# LPEM.net
KiCad netlist of a schematic drawn in EAGLE
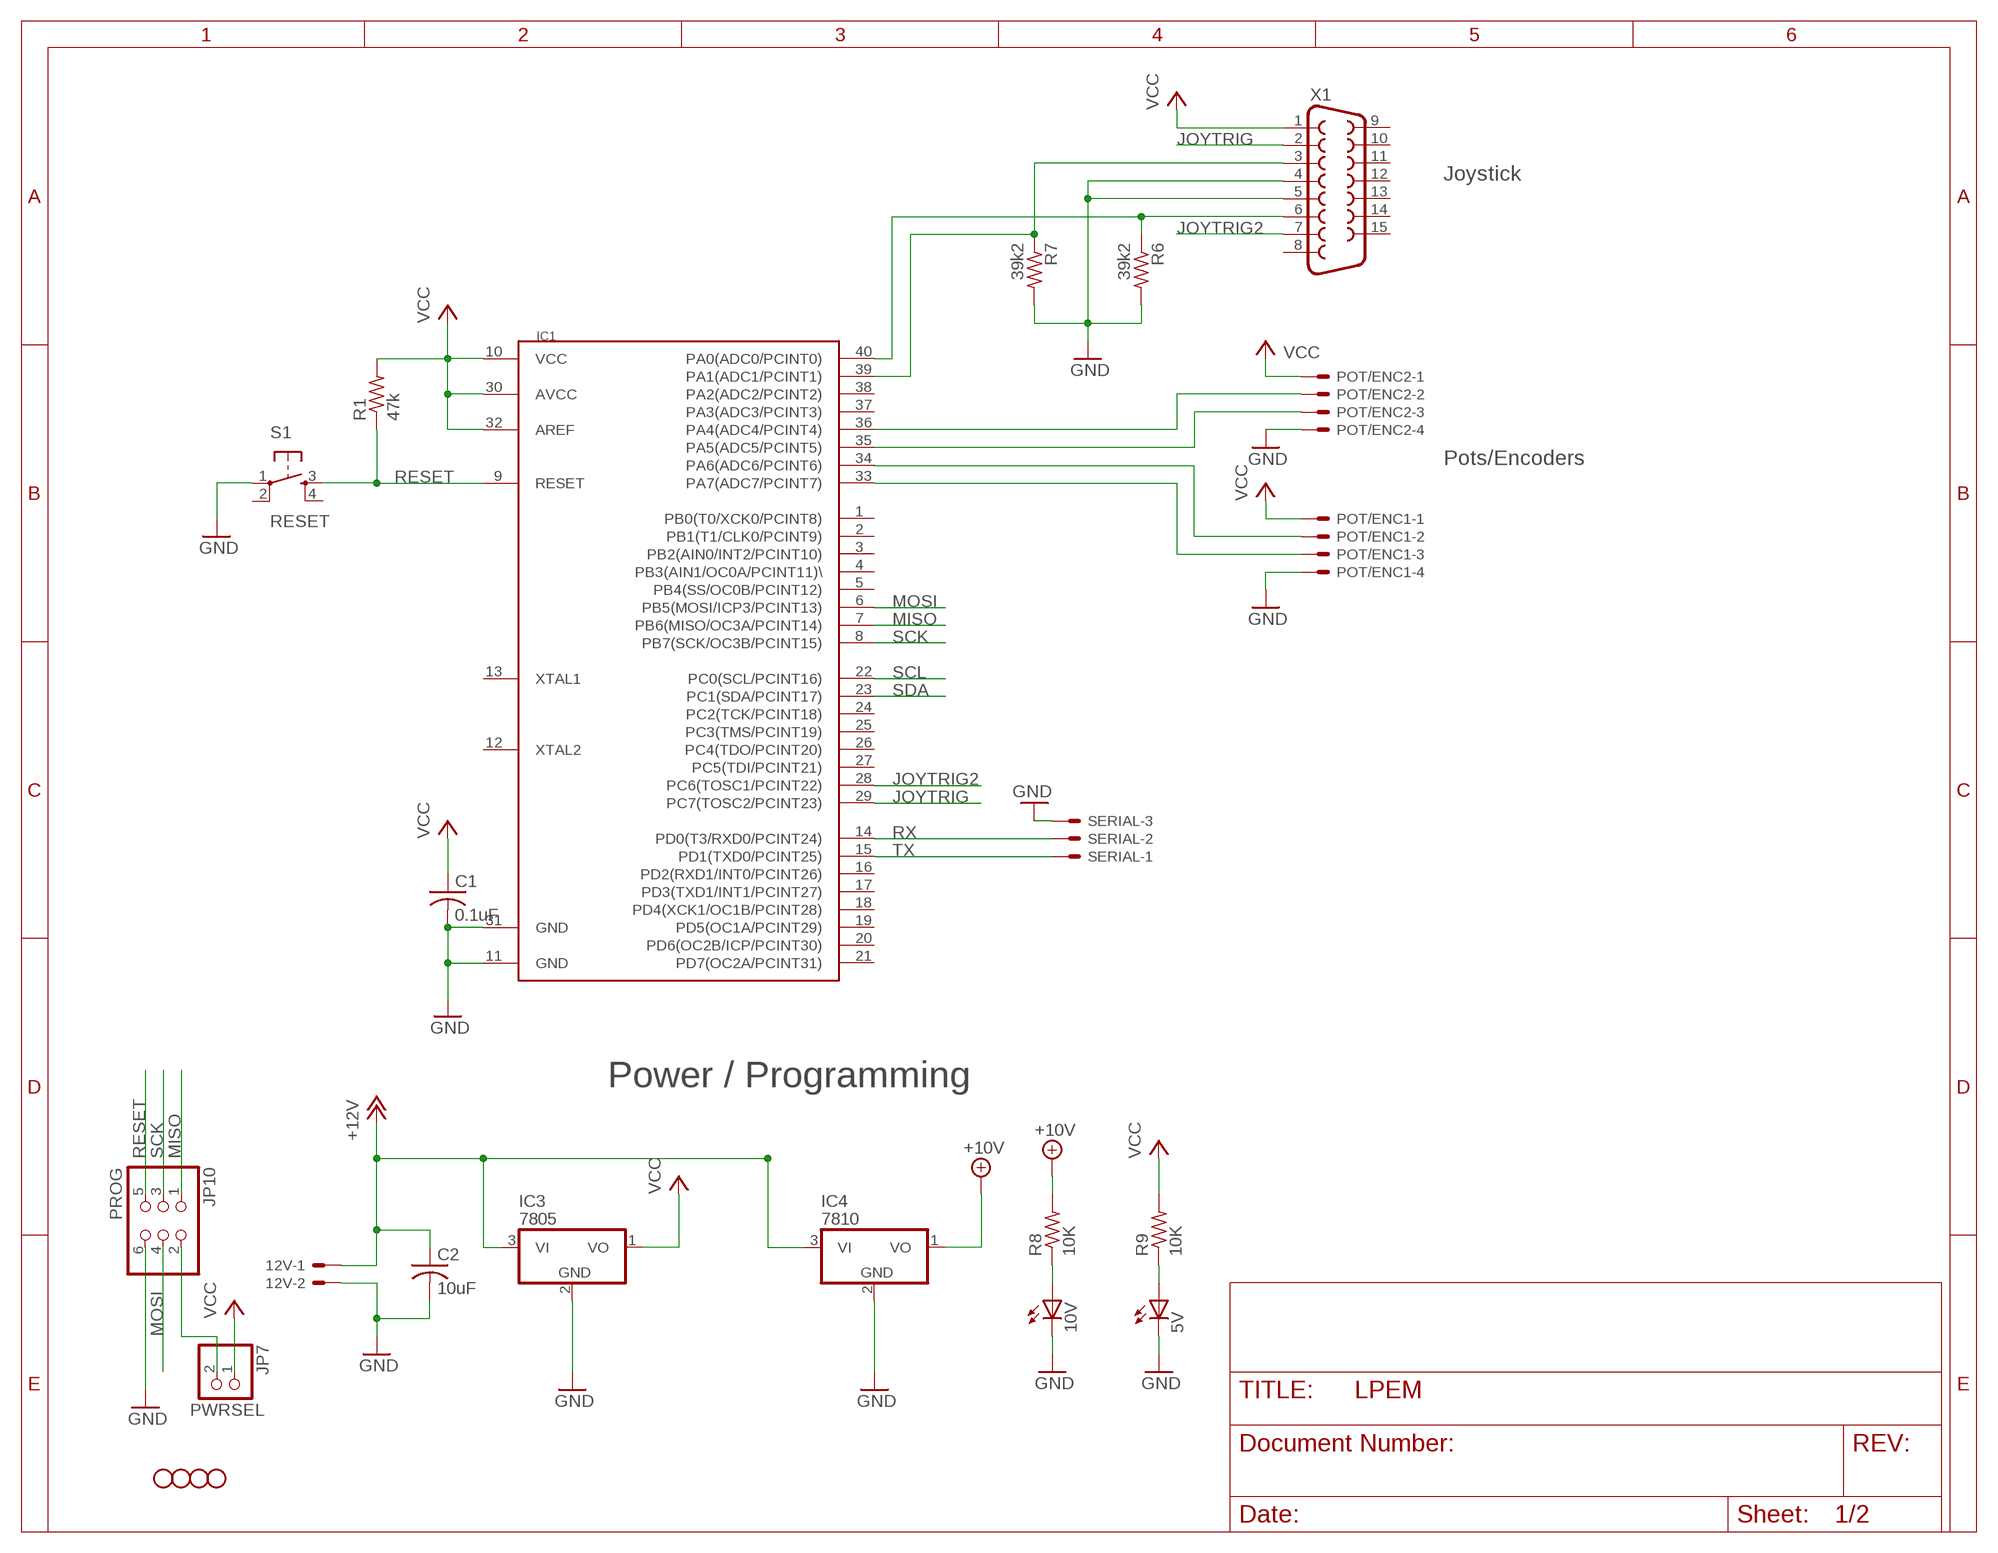
[diagram p0: schematic, sheet 1]
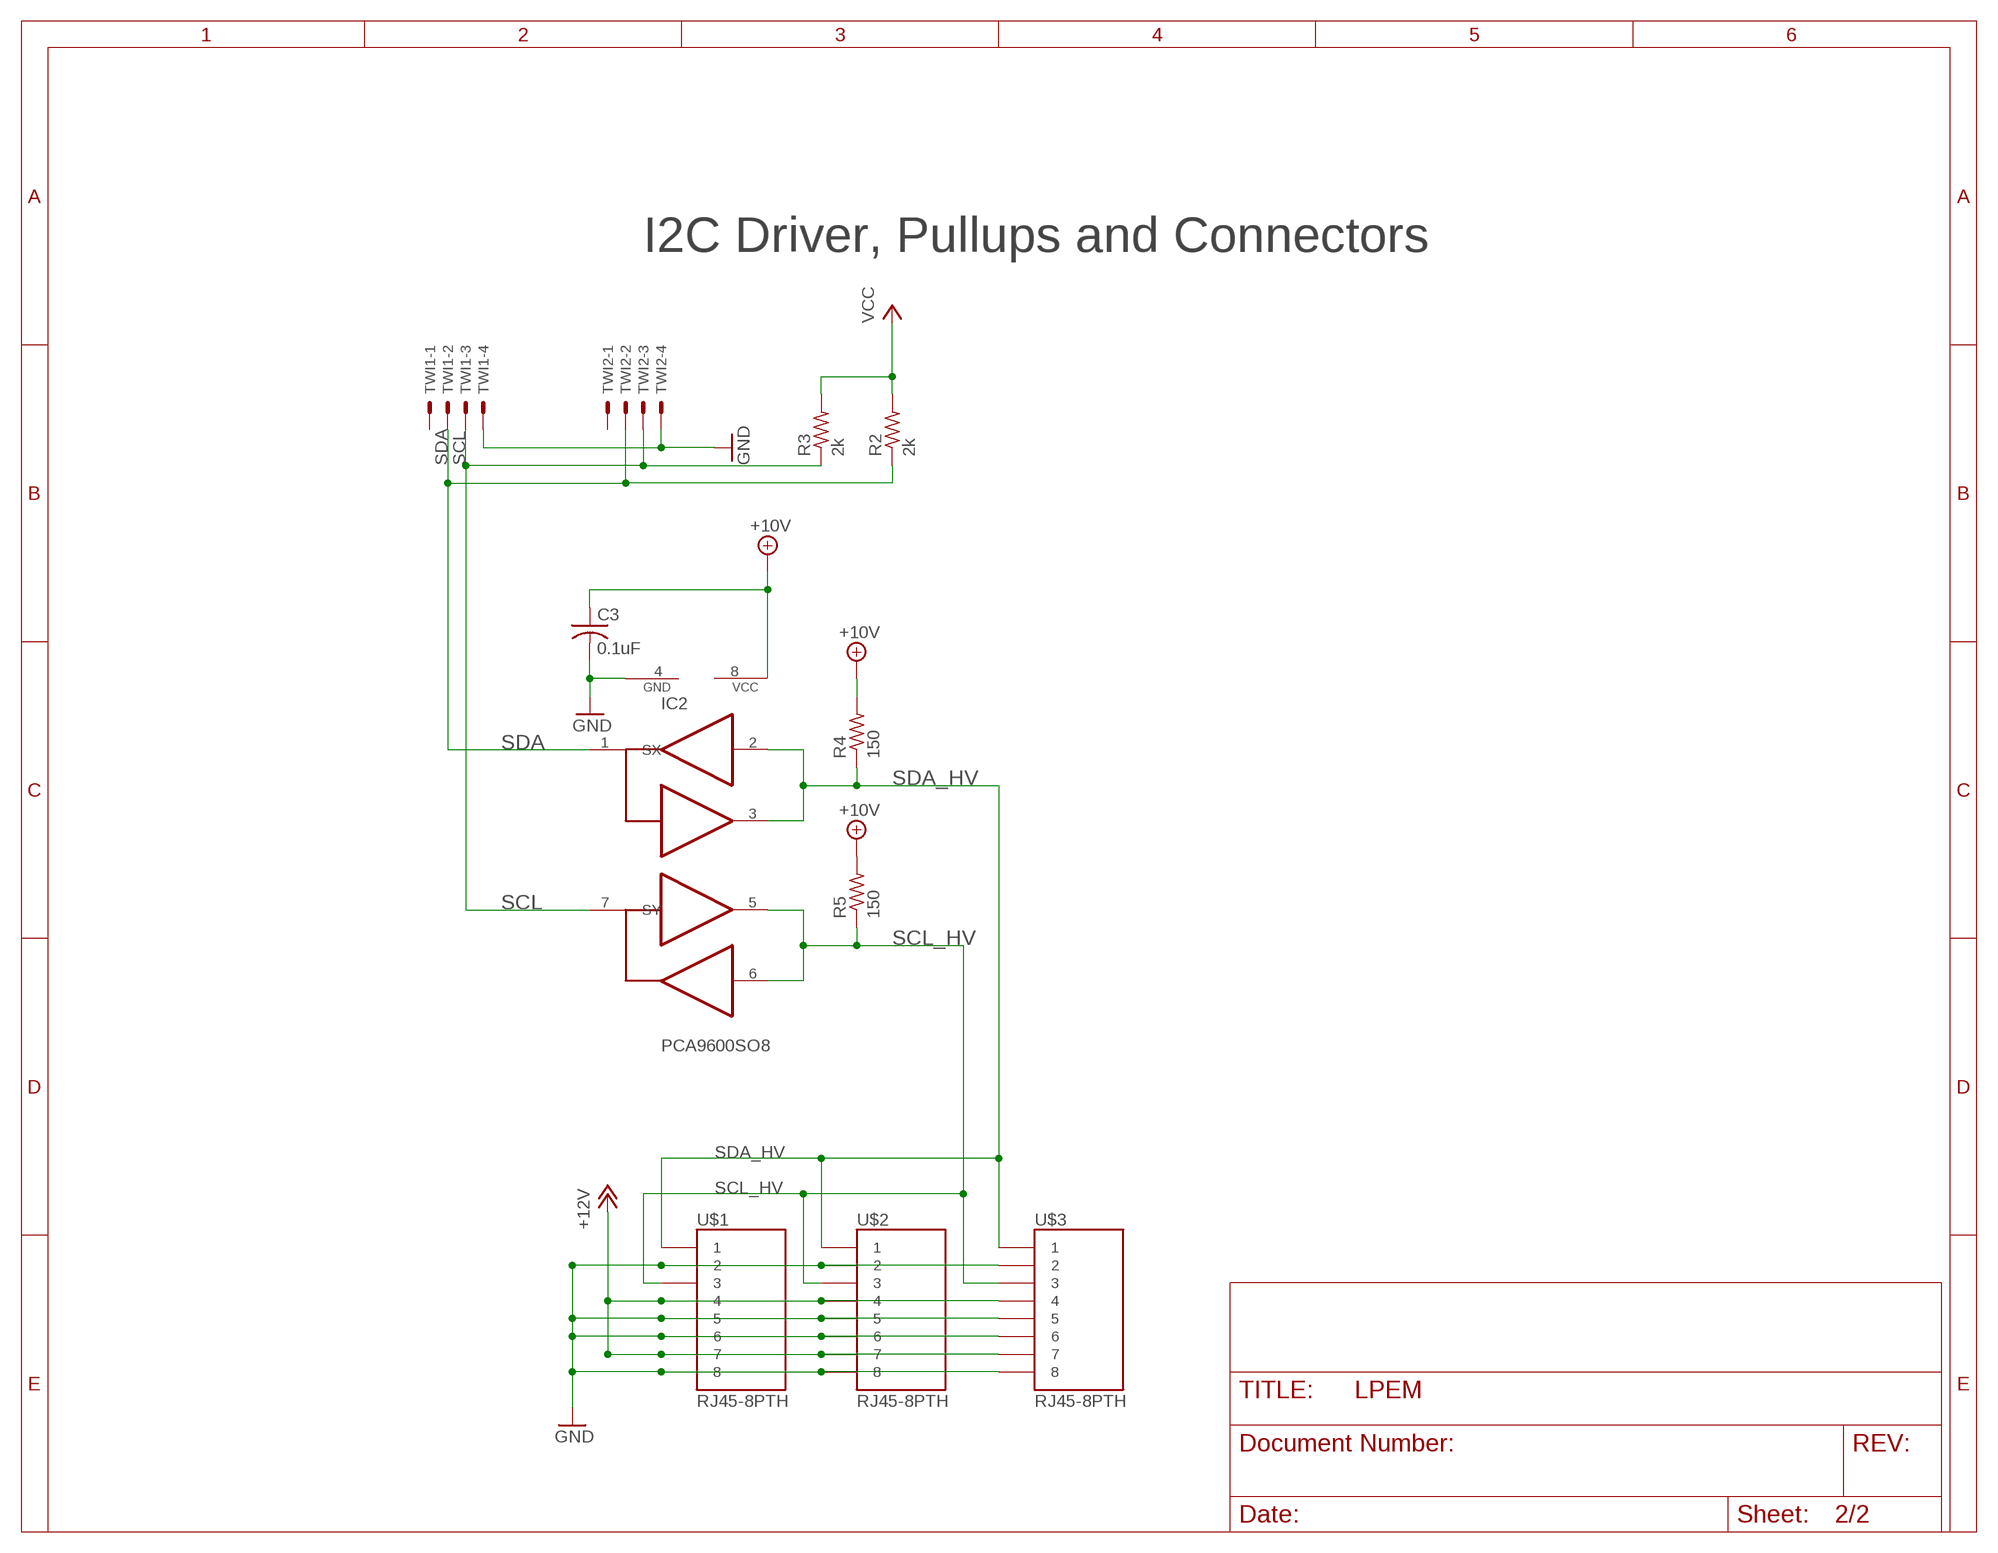
[diagram p1: schematic, sheet 2]

(export (version "E")
  (design (tool "Eeschema 10.0.6"))
  (components
    (comp (ref "5V")
      (value "LED3MM")
      (footprint "eagle-import:LED3MM")
      (libsource (lib "eagle-import") (part "LED3MM"))
    )
    (comp (ref "10V")
      (value "LED3MM")
      (footprint "eagle-import:LED3MM")
      (libsource (lib "eagle-import") (part "LED3MM"))
    )
    (comp (ref "12V")
      (value "22-23-2021")
      (footprint "eagle-import:22-23-2021")
      (fields (field (name "MF") "MOLEX"))
      (libsource (lib "eagle-import") (part "22-23-2021"))
    )
    (comp (ref "C1")
      (value "0.1uF")
      (footprint "eagle-import:C025-025X050")
      (libsource (lib "eagle-import") (part "C-US025-025X050"))
    )
    (comp (ref "C2")
      (value "10uF")
      (footprint "eagle-import:C025-025X050")
      (libsource (lib "eagle-import") (part "C-US025-025X050"))
    )
    (comp (ref "IC1")
      (value "MEGA1284P")
      (footprint "eagle-import:DIL40")
      (libsource (lib "eagle-import") (part "MEGA1284P"))
    )
    (comp (ref "IC3")
      (value "7805")
      (footprint "eagle-import:TO92")
      (libsource (lib "eagle-import") (part "78ZL05"))
    )
    (comp (ref "IC4")
      (value "7810")
      (footprint "eagle-import:TO92")
      (libsource (lib "eagle-import") (part "78ZL05"))
    )
    (comp (ref "JP1")
      (value "STAND-OFF")
      (footprint "eagle-import:STAND-OFF")
      (libsource (lib "eagle-import") (part "STAND-OFF"))
    )
    (comp (ref "JP2")
      (value "STAND-OFF")
      (footprint "eagle-import:STAND-OFF")
      (libsource (lib "eagle-import") (part "STAND-OFF"))
    )
    (comp (ref "JP7")
      (value "PWRSEL")
      (footprint "eagle-import:1X02")
      (libsource (lib "eagle-import") (part "PINHD-1X2"))
    )
    (comp (ref "JP8")
      (value "STAND-OFF")
      (footprint "eagle-import:STAND-OFF")
      (libsource (lib "eagle-import") (part "STAND-OFF"))
    )
    (comp (ref "JP9")
      (value "STAND-OFF")
      (footprint "eagle-import:STAND-OFF")
      (libsource (lib "eagle-import") (part "STAND-OFF"))
    )
    (comp (ref "JP10")
      (value "PROG")
      (footprint "eagle-import:2X03")
      (libsource (lib "eagle-import") (part "PINHD-2X3"))
    )
    (comp (ref "POT/ENC1")
      (value "22-23-2041")
      (footprint "eagle-import:22-23-2041")
      (fields (field (name "MF") "MOLEX"))
      (libsource (lib "eagle-import") (part "22-23-2041"))
    )
    (comp (ref "POT/ENC2")
      (value "22-23-2041")
      (footprint "eagle-import:22-23-2041")
      (fields (field (name "MF") "MOLEX"))
      (libsource (lib "eagle-import") (part "22-23-2041"))
    )
    (comp (ref "R1")
      (value "47k")
      (footprint "eagle-import:0204_5")
      (libsource (lib "eagle-import") (part "R-US_0204/5"))
    )
    (comp (ref "R6")
      (value "39k2")
      (footprint "eagle-import:0204_5")
      (libsource (lib "eagle-import") (part "R-US_0204/5"))
    )
    (comp (ref "R7")
      (value "39k2")
      (footprint "eagle-import:0204_5")
      (libsource (lib "eagle-import") (part "R-US_0204/5"))
    )
    (comp (ref "R8")
      (value "10K")
      (footprint "eagle-import:0204_5")
      (libsource (lib "eagle-import") (part "R-US_0204/5"))
    )
    (comp (ref "R9")
      (value "10K")
      (footprint "eagle-import:0204_5")
      (libsource (lib "eagle-import") (part "R-US_0204/5"))
    )
    (comp (ref "S1")
      (value "RESET")
      (footprint "eagle-import:TACTILE-PTH")
      (libsource (lib "eagle-import") (part "TAC_SWITCHPTH"))
    )
    (comp (ref "SERIAL")
      (value "22-23-2031")
      (footprint "eagle-import:22-23-2031")
      (fields (field (name "MF") "MOLEX"))
      (libsource (lib "eagle-import") (part "22-23-2031"))
    )
    (comp (ref "X1")
      (value "F15HP")
      (footprint "eagle-import:F15HP")
      (libsource (lib "eagle-import") (part "F15HP"))
    )
    (comp (ref "C3")
      (value "0.1uF")
      (footprint "eagle-import:C025-025X050")
      (libsource (lib "eagle-import") (part "C-US025-025X050"))
    )
    (comp (ref "IC2")
      (value "PCA9600SO8")
      (footprint "eagle-import:SO08")
      (libsource (lib "eagle-import") (part "PCA9600SO8"))
    )
    (comp (ref "R2")
      (value "2k")
      (footprint "eagle-import:0204_5")
      (libsource (lib "eagle-import") (part "R-US_0204/5"))
    )
    (comp (ref "R3")
      (value "2k")
      (footprint "eagle-import:0204_5")
      (libsource (lib "eagle-import") (part "R-US_0204/5"))
    )
    (comp (ref "R4")
      (value "150")
      (footprint "eagle-import:0204_5")
      (libsource (lib "eagle-import") (part "R-US_0204/5"))
    )
    (comp (ref "R5")
      (value "150")
      (footprint "eagle-import:0204_5")
      (libsource (lib "eagle-import") (part "R-US_0204/5"))
    )
    (comp (ref "TWI1")
      (value "22-23-2041")
      (footprint "eagle-import:22-23-2041")
      (fields (field (name "MF") "MOLEX"))
      (libsource (lib "eagle-import") (part "22-23-2041"))
    )
    (comp (ref "TWI2")
      (value "22-23-2041")
      (footprint "eagle-import:22-23-2041")
      (fields (field (name "MF") "MOLEX"))
      (libsource (lib "eagle-import") (part "22-23-2041"))
    )
    (comp (ref "U$1")
      (value "RJ45-8PTH")
      (footprint "eagle-import:RJ45-8")
      (libsource (lib "eagle-import") (part "RJ45-8PTH"))
    )
    (comp (ref "U$2")
      (value "RJ45-8PTH")
      (footprint "eagle-import:RJ45-8")
      (libsource (lib "eagle-import") (part "RJ45-8PTH"))
    )
    (comp (ref "U$3")
      (value "RJ45-8PTH")
      (footprint "eagle-import:RJ45-8")
      (libsource (lib "eagle-import") (part "RJ45-8PTH"))
    )
  )
  (nets
    (net (code "1") (name "+10V") (class "Default")
      (node (ref "C3") (pin "1") (pinfunction "1_1") (pintype "passive"))
      (node (ref "IC2") (pin "8") (pinfunction "VCC_8") (pintype "power_in"))
      (node (ref "IC4") (pin "1") (pinfunction "VO_1") (pintype "passive"))
      (node (ref "R4") (pin "2") (pinfunction "2_2") (pintype "passive"))
      (node (ref "R5") (pin "2") (pinfunction "2_2") (pintype "passive"))
      (node (ref "R8") (pin "2") (pinfunction "2_2") (pintype "passive"))
    )
    (net (code "2") (name "+12V") (class "Default")
      (node (ref "12V") (pin "1") (pinfunction "S_1") (pintype "passive"))
      (node (ref "C2") (pin "1") (pinfunction "1_1") (pintype "passive"))
      (node (ref "IC3") (pin "3") (pinfunction "VI_3") (pintype "input"))
      (node (ref "IC4") (pin "3") (pinfunction "VI_3") (pintype "input"))
      (node (ref "U$1") (pin "4") (pinfunction "4_4") (pintype "bidirectional"))
      (node (ref "U$1") (pin "7") (pinfunction "7_7") (pintype "bidirectional"))
      (node (ref "U$2") (pin "4") (pinfunction "4_4") (pintype "bidirectional"))
      (node (ref "U$2") (pin "7") (pinfunction "7_7") (pintype "bidirectional"))
      (node (ref "U$3") (pin "4") (pinfunction "4_4") (pintype "bidirectional"))
      (node (ref "U$3") (pin "7") (pinfunction "7_7") (pintype "bidirectional"))
    )
    (net (code "3") (name "GND") (class "Default")
      (node (ref "10V") (pin "K") (pinfunction "C_K") (pintype "passive"))
      (node (ref "12V") (pin "2") (pinfunction "S_2") (pintype "passive"))
      (node (ref "5V") (pin "K") (pinfunction "C_K") (pintype "passive"))
      (node (ref "C1") (pin "2") (pinfunction "2_2") (pintype "passive"))
      (node (ref "C2") (pin "2") (pinfunction "2_2") (pintype "passive"))
      (node (ref "C3") (pin "2") (pinfunction "2_2") (pintype "passive"))
      (node (ref "IC1") (pin "11") (pinfunction "GND_11") (pintype "bidirectional"))
      (node (ref "IC1") (pin "31") (pinfunction "GND_31") (pintype "bidirectional"))
      (node (ref "IC2") (pin "4") (pinfunction "GND_4") (pintype "power_in"))
      (node (ref "IC3") (pin "2") (pinfunction "GND_2") (pintype "passive"))
      (node (ref "IC4") (pin "2") (pinfunction "GND_2") (pintype "passive"))
      (node (ref "JP10") (pin "6") (pinfunction "6_6") (pintype "passive"))
      (node (ref "POT/ENC1") (pin "4") (pinfunction "S_4") (pintype "passive"))
      (node (ref "POT/ENC2") (pin "4") (pinfunction "S_4") (pintype "passive"))
      (node (ref "R6") (pin "2") (pinfunction "2_2") (pintype "passive"))
      (node (ref "R7") (pin "2") (pinfunction "2_2") (pintype "passive"))
      (node (ref "S1") (pin "1") (pinfunction "1_1") (pintype "passive"))
      (node (ref "SERIAL") (pin "3") (pinfunction "S_3") (pintype "passive"))
      (node (ref "TWI1") (pin "4") (pinfunction "S_4") (pintype "passive"))
      (node (ref "TWI2") (pin "4") (pinfunction "S_4") (pintype "passive"))
      (node (ref "U$1") (pin "2") (pinfunction "2_2") (pintype "bidirectional"))
      (node (ref "U$1") (pin "5") (pinfunction "5_5") (pintype "bidirectional"))
      (node (ref "U$1") (pin "6") (pinfunction "6_6") (pintype "bidirectional"))
      (node (ref "U$1") (pin "8") (pinfunction "8_8") (pintype "bidirectional"))
      (node (ref "U$2") (pin "2") (pinfunction "2_2") (pintype "bidirectional"))
      (node (ref "U$2") (pin "5") (pinfunction "5_5") (pintype "bidirectional"))
      (node (ref "U$2") (pin "6") (pinfunction "6_6") (pintype "bidirectional"))
      (node (ref "U$2") (pin "8") (pinfunction "8_8") (pintype "bidirectional"))
      (node (ref "U$3") (pin "2") (pinfunction "2_2") (pintype "bidirectional"))
      (node (ref "U$3") (pin "5") (pinfunction "5_5") (pintype "bidirectional"))
      (node (ref "U$3") (pin "6") (pinfunction "6_6") (pintype "bidirectional"))
      (node (ref "U$3") (pin "8") (pinfunction "8_8") (pintype "bidirectional"))
      (node (ref "X1") (pin "4") (pinfunction "4_4") (pintype "passive"))
      (node (ref "X1") (pin "5") (pinfunction "5_5") (pintype "passive"))
    )
    (net (code "4") (name "JOYTRIG") (class "Default")
      (node (ref "IC1") (pin "29") (pinfunction "PC7(TOSC2/PCINT23)_29") (pintype "bidirectional"))
      (node (ref "X1") (pin "2") (pinfunction "2_2") (pintype "passive"))
    )
    (net (code "5") (name "JOYTRIG2") (class "Default")
      (node (ref "IC1") (pin "28") (pinfunction "PC6(TOSC1/PCINT22)_28") (pintype "bidirectional"))
      (node (ref "X1") (pin "7") (pinfunction "7_7") (pintype "passive"))
    )
    (net (code "6") (name "MISO") (class "Default")
      (node (ref "IC1") (pin "7") (pinfunction "PB6(MISO/OC3A/PCINT14)_7") (pintype "bidirectional"))
      (node (ref "JP10") (pin "1") (pinfunction "1_1") (pintype "passive"))
    )
    (net (code "7") (name "MOSI") (class "Default")
      (node (ref "IC1") (pin "6") (pinfunction "PB5(MOSI/ICP3/PCINT13)_6") (pintype "bidirectional"))
      (node (ref "JP10") (pin "4") (pinfunction "4_4") (pintype "passive"))
    )
    (net (code "8") (name "Net-(5V-PadA)") (class "Default")
      (node (ref "5V") (pin "A") (pinfunction "A_A") (pintype "passive"))
      (node (ref "R9") (pin "1") (pinfunction "1_1") (pintype "passive"))
    )
    (net (code "9") (name "Net-(10V-PadA)") (class "Default")
      (node (ref "10V") (pin "A") (pinfunction "A_A") (pintype "passive"))
      (node (ref "R8") (pin "1") (pinfunction "1_1") (pintype "passive"))
    )
    (net (code "10") (name "Net-(IC1-PA0(ADC0{slash}PCINT0))") (class "Default")
      (node (ref "IC1") (pin "40") (pinfunction "PA0(ADC0/PCINT0)_40") (pintype "bidirectional"))
      (node (ref "R6") (pin "1") (pinfunction "1_1") (pintype "passive"))
      (node (ref "X1") (pin "6") (pinfunction "6_6") (pintype "passive"))
    )
    (net (code "11") (name "Net-(IC1-PA1(ADC1{slash}PCINT1))") (class "Default")
      (node (ref "IC1") (pin "39") (pinfunction "PA1(ADC1/PCINT1)_39") (pintype "bidirectional"))
      (node (ref "R7") (pin "1") (pinfunction "1_1") (pintype "passive"))
      (node (ref "X1") (pin "3") (pinfunction "3_3") (pintype "passive"))
    )
    (net (code "12") (name "Net-(IC1-PA4(ADC4{slash}PCINT4))") (class "Default")
      (node (ref "IC1") (pin "36") (pinfunction "PA4(ADC4/PCINT4)_36") (pintype "bidirectional"))
      (node (ref "POT/ENC2") (pin "2") (pinfunction "S_2") (pintype "passive"))
    )
    (net (code "13") (name "Net-(IC1-PA5(ADC5{slash}PCINT5))") (class "Default")
      (node (ref "IC1") (pin "35") (pinfunction "PA5(ADC5/PCINT5)_35") (pintype "bidirectional"))
      (node (ref "POT/ENC2") (pin "3") (pinfunction "S_3") (pintype "passive"))
    )
    (net (code "14") (name "Net-(IC1-PA6(ADC6{slash}PCINT6))") (class "Default")
      (node (ref "IC1") (pin "34") (pinfunction "PA6(ADC6/PCINT6)_34") (pintype "bidirectional"))
      (node (ref "POT/ENC1") (pin "2") (pinfunction "S_2") (pintype "passive"))
    )
    (net (code "15") (name "Net-(IC1-PA7(ADC7{slash}PCINT7))") (class "Default")
      (node (ref "IC1") (pin "33") (pinfunction "PA7(ADC7/PCINT7)_33") (pintype "bidirectional"))
      (node (ref "POT/ENC1") (pin "3") (pinfunction "S_3") (pintype "passive"))
    )
    (net (code "16") (name "Net-(JP10-Pad2)") (class "Default")
      (node (ref "JP10") (pin "2") (pinfunction "2_2") (pintype "passive"))
      (node (ref "JP7") (pin "2") (pinfunction "2_2") (pintype "passive"))
    )
    (net (code "17") (name "RESET") (class "Default")
      (node (ref "IC1") (pin "9") (pinfunction "RESET_9") (pintype "bidirectional"))
      (node (ref "JP10") (pin "5") (pinfunction "5_5") (pintype "passive"))
      (node (ref "R1") (pin "1") (pinfunction "1_1") (pintype "passive"))
      (node (ref "S1") (pin "3") (pinfunction "3_3") (pintype "passive"))
    )
    (net (code "18") (name "RX") (class "Default")
      (node (ref "IC1") (pin "14") (pinfunction "PD0(T3/RXD0/PCINT24)_14") (pintype "bidirectional"))
      (node (ref "SERIAL") (pin "2") (pinfunction "S_2") (pintype "passive"))
    )
    (net (code "19") (name "SCK") (class "Default")
      (node (ref "IC1") (pin "8") (pinfunction "PB7(SCK/OC3B/PCINT15)_8") (pintype "bidirectional"))
      (node (ref "JP10") (pin "3") (pinfunction "3_3") (pintype "passive"))
    )
    (net (code "20") (name "SCL") (class "Default")
      (node (ref "IC1") (pin "22") (pinfunction "PC0(SCL/PCINT16)_22") (pintype "bidirectional"))
      (node (ref "IC2") (pin "7") (pinfunction "SY_7") (pintype "bidirectional"))
      (node (ref "R3") (pin "1") (pinfunction "1_1") (pintype "passive"))
      (node (ref "TWI1") (pin "3") (pinfunction "S_3") (pintype "passive"))
      (node (ref "TWI2") (pin "3") (pinfunction "S_3") (pintype "passive"))
    )
    (net (code "21") (name "SCL_HV") (class "Default")
      (node (ref "IC2") (pin "5") (pinfunction "TY_5") (pintype "output"))
      (node (ref "IC2") (pin "6") (pinfunction "RY_6") (pintype "input"))
      (node (ref "R5") (pin "1") (pinfunction "1_1") (pintype "passive"))
      (node (ref "U$1") (pin "3") (pinfunction "3_3") (pintype "bidirectional"))
      (node (ref "U$2") (pin "3") (pinfunction "3_3") (pintype "bidirectional"))
      (node (ref "U$3") (pin "3") (pinfunction "3_3") (pintype "bidirectional"))
    )
    (net (code "22") (name "SDA") (class "Default")
      (node (ref "IC1") (pin "23") (pinfunction "PC1(SDA/PCINT17)_23") (pintype "bidirectional"))
      (node (ref "IC2") (pin "1") (pinfunction "SX_1") (pintype "bidirectional"))
      (node (ref "R2") (pin "1") (pinfunction "1_1") (pintype "passive"))
      (node (ref "TWI1") (pin "2") (pinfunction "S_2") (pintype "passive"))
      (node (ref "TWI2") (pin "2") (pinfunction "S_2") (pintype "passive"))
    )
    (net (code "23") (name "SDA_HV") (class "Default")
      (node (ref "IC2") (pin "2") (pinfunction "RX_2") (pintype "input"))
      (node (ref "IC2") (pin "3") (pinfunction "TX_3") (pintype "output"))
      (node (ref "R4") (pin "1") (pinfunction "1_1") (pintype "passive"))
      (node (ref "U$1") (pin "1") (pinfunction "1_1") (pintype "bidirectional"))
      (node (ref "U$2") (pin "1") (pinfunction "1_1") (pintype "bidirectional"))
      (node (ref "U$3") (pin "1") (pinfunction "1_1") (pintype "bidirectional"))
    )
    (net (code "24") (name "TX") (class "Default")
      (node (ref "IC1") (pin "15") (pinfunction "PD1(TXD0/PCINT25)_15") (pintype "bidirectional"))
      (node (ref "SERIAL") (pin "1") (pinfunction "S_1") (pintype "passive"))
    )
    (net (code "25") (name "VCC") (class "Default")
      (node (ref "C1") (pin "1") (pinfunction "1_1") (pintype "passive"))
      (node (ref "IC1") (pin "10") (pinfunction "VCC_10") (pintype "bidirectional"))
      (node (ref "IC1") (pin "30") (pinfunction "AVCC_30") (pintype "bidirectional"))
      (node (ref "IC1") (pin "32") (pinfunction "AREF_32") (pintype "bidirectional"))
      (node (ref "IC3") (pin "1") (pinfunction "VO_1") (pintype "passive"))
      (node (ref "JP7") (pin "1") (pinfunction "1_1") (pintype "passive"))
      (node (ref "POT/ENC1") (pin "1") (pinfunction "S_1") (pintype "passive"))
      (node (ref "POT/ENC2") (pin "1") (pinfunction "S_1") (pintype "passive"))
      (node (ref "R1") (pin "2") (pinfunction "2_2") (pintype "passive"))
      (node (ref "R2") (pin "2") (pinfunction "2_2") (pintype "passive"))
      (node (ref "R3") (pin "2") (pinfunction "2_2") (pintype "passive"))
      (node (ref "R9") (pin "2") (pinfunction "2_2") (pintype "passive"))
      (node (ref "X1") (pin "1") (pinfunction "1_1") (pintype "passive"))
    )
    (net (code "26") (name "unconnected-(IC1-PA2(ADC2{slash}PCINT2)-Pad38)") (class "Default")
      (node (ref "IC1") (pin "38") (pinfunction "PA2(ADC2/PCINT2)_38") (pintype "bidirectional"))
    )
    (net (code "27") (name "unconnected-(IC1-PA3(ADC3{slash}PCINT3)-Pad37)") (class "Default")
      (node (ref "IC1") (pin "37") (pinfunction "PA3(ADC3/PCINT3)_37") (pintype "bidirectional"))
    )
    (net (code "28") (name "unconnected-(IC1-PB0(T0{slash}XCK0{slash}PCINT8)-Pad1)") (class "Default")
      (node (ref "IC1") (pin "1") (pinfunction "PB0(T0/XCK0/PCINT8)_1") (pintype "bidirectional"))
    )
    (net (code "29") (name "unconnected-(IC1-PB1(T1{slash}CLK0{slash}PCINT9)-Pad2)") (class "Default")
      (node (ref "IC1") (pin "2") (pinfunction "PB1(T1/CLK0/PCINT9)_2") (pintype "bidirectional"))
    )
    (net (code "30") (name "unconnected-(IC1-PB2(AIN0{slash}INT2{slash}PCINT10)-Pad3)") (class "Default")
      (node (ref "IC1") (pin "3") (pinfunction "PB2(AIN0/INT2/PCINT10)_3") (pintype "bidirectional"))
    )
    (net (code "31") (name "unconnected-(IC1-PB3(AIN1{slash}OC0A{slash}PCINT11)\\-Pad4)") (class "Default")
      (node (ref "IC1") (pin "4") (pinfunction "PB3(AIN1/OC0A/PCINT11)\\_4") (pintype "bidirectional"))
    )
    (net (code "32") (name "unconnected-(IC1-PB4(SS{slash}OC0B{slash}PCINT12)-Pad5)") (class "Default")
      (node (ref "IC1") (pin "5") (pinfunction "PB4(SS/OC0B/PCINT12)_5") (pintype "bidirectional"))
    )
    (net (code "33") (name "unconnected-(IC1-PC2(TCK{slash}PCINT18)-Pad24)") (class "Default")
      (node (ref "IC1") (pin "24") (pinfunction "PC2(TCK/PCINT18)_24") (pintype "bidirectional"))
    )
    (net (code "34") (name "unconnected-(IC1-PC3(TMS{slash}PCINT19)-Pad25)") (class "Default")
      (node (ref "IC1") (pin "25") (pinfunction "PC3(TMS/PCINT19)_25") (pintype "bidirectional"))
    )
    (net (code "35") (name "unconnected-(IC1-PC4(TDO{slash}PCINT20)-Pad26)") (class "Default")
      (node (ref "IC1") (pin "26") (pinfunction "PC4(TDO/PCINT20)_26") (pintype "bidirectional"))
    )
    (net (code "36") (name "unconnected-(IC1-PC5(TDI{slash}PCINT21)-Pad27)") (class "Default")
      (node (ref "IC1") (pin "27") (pinfunction "PC5(TDI/PCINT21)_27") (pintype "bidirectional"))
    )
    (net (code "37") (name "unconnected-(IC1-PD2(RXD1{slash}INT0{slash}PCINT26)-Pad16)") (class "Default")
      (node (ref "IC1") (pin "16") (pinfunction "PD2(RXD1/INT0/PCINT26)_16") (pintype "bidirectional"))
    )
    (net (code "38") (name "unconnected-(IC1-PD3(TXD1{slash}INT1{slash}PCINT27)-Pad17)") (class "Default")
      (node (ref "IC1") (pin "17") (pinfunction "PD3(TXD1/INT1/PCINT27)_17") (pintype "bidirectional"))
    )
    (net (code "39") (name "unconnected-(IC1-PD4(XCK1{slash}OC1B{slash}PCINT28)-Pad18)") (class "Default")
      (node (ref "IC1") (pin "18") (pinfunction "PD4(XCK1/OC1B/PCINT28)_18") (pintype "bidirectional"))
    )
    (net (code "40") (name "unconnected-(IC1-PD5(OC1A{slash}PCINT29)-Pad19)") (class "Default")
      (node (ref "IC1") (pin "19") (pinfunction "PD5(OC1A/PCINT29)_19") (pintype "bidirectional"))
    )
    (net (code "41") (name "unconnected-(IC1-PD6(OC2B{slash}ICP{slash}PCINT30)-Pad20)") (class "Default")
      (node (ref "IC1") (pin "20") (pinfunction "PD6(OC2B/ICP/PCINT30)_20") (pintype "bidirectional"))
    )
    (net (code "42") (name "unconnected-(IC1-PD7(OC2A{slash}PCINT31)-Pad21)") (class "Default")
      (node (ref "IC1") (pin "21") (pinfunction "PD7(OC2A/PCINT31)_21") (pintype "bidirectional"))
    )
    (net (code "43") (name "unconnected-(IC1-XTAL1-Pad13)") (class "Default")
      (node (ref "IC1") (pin "13") (pinfunction "XTAL1_13") (pintype "bidirectional"))
    )
    (net (code "44") (name "unconnected-(IC1-XTAL2-Pad12)") (class "Default")
      (node (ref "IC1") (pin "12") (pinfunction "XTAL2_12") (pintype "bidirectional"))
    )
    (net (code "45") (name "unconnected-(S1-Pad2)") (class "Default")
      (node (ref "S1") (pin "2") (pinfunction "2_2") (pintype "passive"))
    )
    (net (code "46") (name "unconnected-(S1-Pad4)") (class "Default")
      (node (ref "S1") (pin "4") (pinfunction "4_4") (pintype "passive"))
    )
    (net (code "47") (name "unconnected-(TWI1A-S-Pad1)") (class "Default")
      (node (ref "TWI1") (pin "1") (pinfunction "S_1") (pintype "passive"))
    )
    (net (code "48") (name "unconnected-(TWI2A-S-Pad1)") (class "Default")
      (node (ref "TWI2") (pin "1") (pinfunction "S_1") (pintype "passive"))
    )
    (net (code "49") (name "unconnected-(X1-Pad8)") (class "Default")
      (node (ref "X1") (pin "8") (pinfunction "8_8") (pintype "passive"))
    )
    (net (code "50") (name "unconnected-(X1-Pad9)") (class "Default")
      (node (ref "X1") (pin "9") (pinfunction "9_9") (pintype "passive"))
    )
    (net (code "51") (name "unconnected-(X1-Pad10)") (class "Default")
      (node (ref "X1") (pin "10") (pinfunction "10_10") (pintype "passive"))
    )
    (net (code "52") (name "unconnected-(X1-Pad11)") (class "Default")
      (node (ref "X1") (pin "11") (pinfunction "11_11") (pintype "passive"))
    )
    (net (code "53") (name "unconnected-(X1-Pad12)") (class "Default")
      (node (ref "X1") (pin "12") (pinfunction "12_12") (pintype "passive"))
    )
    (net (code "54") (name "unconnected-(X1-Pad13)") (class "Default")
      (node (ref "X1") (pin "13") (pinfunction "13_13") (pintype "passive"))
    )
    (net (code "55") (name "unconnected-(X1-Pad14)") (class "Default")
      (node (ref "X1") (pin "14") (pinfunction "14_14") (pintype "passive"))
    )
    (net (code "56") (name "unconnected-(X1-Pad15)") (class "Default")
      (node (ref "X1") (pin "15") (pinfunction "15_15") (pintype "passive"))
    )
  )
)
